# ECG_Monitor.net
KiCad netlist of a schematic drawn in Altium Designer
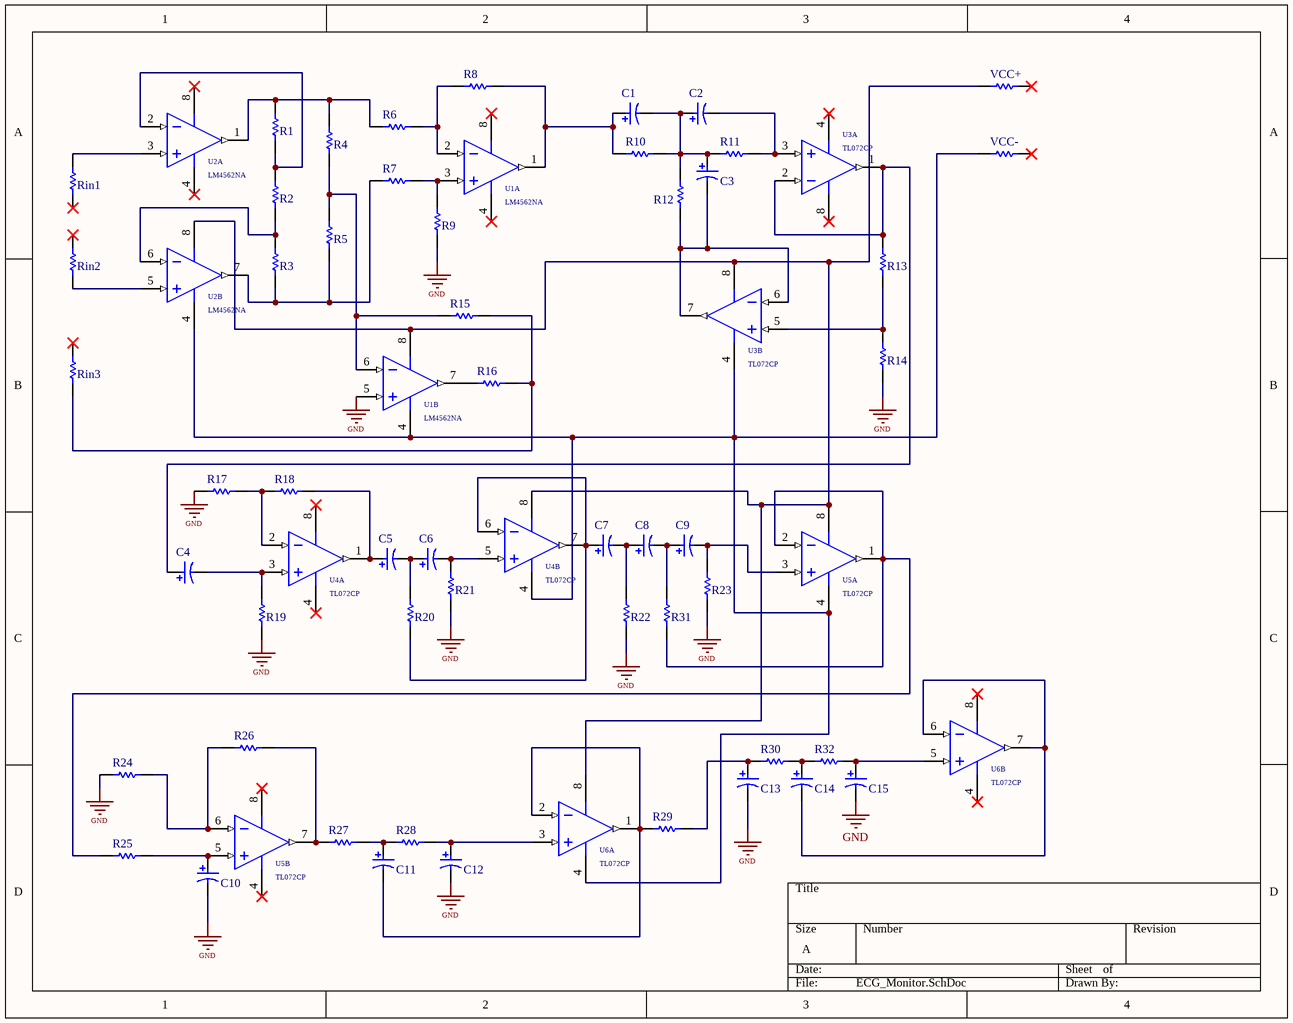
[diagram p0: ECG_Monitor.SchDoc]

(export (version "E")
  (design (tool "Eeschema 10.0.6"))
  (components
    (comp (ref "C1")
      (value "ECA1HM100")
      (footprint "CAPPR55-200-1100X500X1200")
      (description "Aluminum Electrolytic Capacitor, 10 uF, +/- 20%, 50 V, -40 to 85 degC, 2-Pin THD, RoHS, Bulk")
      (fields (field (name "MANUFACTURER") "Panasonic") (field (name "TOLERANCE") "20%"))
      (libsource (lib "Altium Content Vault") (part "CAP-P-2"))
    )
    (comp (ref "C2")
      (value "ECA1HM100")
      (footprint "CAPPR55-200-1100X500X1200")
      (description "Aluminum Electrolytic Capacitor, 10 uF, +/- 20%, 50 V, -40 to 85 degC, 2-Pin THD, RoHS, Bulk")
      (fields (field (name "MANUFACTURER") "Panasonic") (field (name "TOLERANCE") "20%"))
      (libsource (lib "Altium Content Vault") (part "CAP-P-2"))
    )
    (comp (ref "C3")
      (value "ECA1HM100")
      (footprint "CAPPR55-200-1100X500X1200")
      (description "Aluminum Electrolytic Capacitor, 10 uF, +/- 20%, 50 V, -40 to 85 degC, 2-Pin THD, RoHS, Bulk")
      (fields (field (name "MANUFACTURER") "Panasonic") (field (name "TOLERANCE") "20%"))
      (libsource (lib "Altium Content Vault") (part "CAP-P-2"))
    )
    (comp (ref "C4")
      (value "ECA1HM100")
      (footprint "CAPPR55-200-1100X500X1200")
      (description "Aluminum Electrolytic Capacitor, 10 uF, +/- 20%, 50 V, -40 to 85 degC, 2-Pin THD, RoHS, Bulk")
      (fields (field (name "MANUFACTURER") "Panasonic") (field (name "TOLERANCE") "20%"))
      (libsource (lib "Altium Content Vault") (part "CAP-P-2"))
    )
    (comp (ref "C5")
      (value "ECA1HM100")
      (footprint "CAPPR55-200-1100X500X1200")
      (description "Aluminum Electrolytic Capacitor, 10 uF, +/- 20%, 50 V, -40 to 85 degC, 2-Pin THD, RoHS, Bulk")
      (fields (field (name "MANUFACTURER") "Panasonic") (field (name "TOLERANCE") "20%"))
      (libsource (lib "Altium Content Vault") (part "CAP-P-2"))
    )
    (comp (ref "C6")
      (value "ECA1HM100")
      (footprint "CAPPR55-200-1100X500X1200")
      (description "Aluminum Electrolytic Capacitor, 10 uF, +/- 20%, 50 V, -40 to 85 degC, 2-Pin THD, RoHS, Bulk")
      (fields (field (name "MANUFACTURER") "Panasonic") (field (name "TOLERANCE") "20%"))
      (libsource (lib "Altium Content Vault") (part "CAP-P-2"))
    )
    (comp (ref "C7")
      (value "ECA1HM100")
      (footprint "CAPPR55-200-1100X500X1200")
      (description "Aluminum Electrolytic Capacitor, 10 uF, +/- 20%, 50 V, -40 to 85 degC, 2-Pin THD, RoHS, Bulk")
      (fields (field (name "MANUFACTURER") "Panasonic") (field (name "TOLERANCE") "20%"))
      (libsource (lib "Altium Content Vault") (part "CAP-P-2"))
    )
    (comp (ref "C8")
      (value "ECA1HM100")
      (footprint "CAPPR55-200-1100X500X1200")
      (description "Aluminum Electrolytic Capacitor, 10 uF, +/- 20%, 50 V, -40 to 85 degC, 2-Pin THD, RoHS, Bulk")
      (fields (field (name "MANUFACTURER") "Panasonic") (field (name "TOLERANCE") "20%"))
      (libsource (lib "Altium Content Vault") (part "CAP-P-2"))
    )
    (comp (ref "C9")
      (value "ECA1HM100")
      (footprint "CAPPR55-200-1100X500X1200")
      (description "Aluminum Electrolytic Capacitor, 10 uF, +/- 20%, 50 V, -40 to 85 degC, 2-Pin THD, RoHS, Bulk")
      (fields (field (name "MANUFACTURER") "Panasonic") (field (name "TOLERANCE") "20%"))
      (libsource (lib "Altium Content Vault") (part "CAP-P-2"))
    )
    (comp (ref "C10")
      (value "ECA1HM100")
      (footprint "CAPPR55-200-1100X500X1200")
      (description "Aluminum Electrolytic Capacitor, 10 uF, +/- 20%, 50 V, -40 to 85 degC, 2-Pin THD, RoHS, Bulk")
      (fields (field (name "MANUFACTURER") "Panasonic") (field (name "TOLERANCE") "20%"))
      (libsource (lib "Altium Content Vault") (part "CAP-P-2"))
    )
    (comp (ref "C11")
      (value "ECA1HM100")
      (footprint "CAPPR55-200-1100X500X1200")
      (description "Aluminum Electrolytic Capacitor, 10 uF, +/- 20%, 50 V, -40 to 85 degC, 2-Pin THD, RoHS, Bulk")
      (fields (field (name "MANUFACTURER") "Panasonic") (field (name "TOLERANCE") "20%"))
      (libsource (lib "Altium Content Vault") (part "CAP-P-2"))
    )
    (comp (ref "C12")
      (value "ECA1HM100")
      (footprint "CAPPR55-200-1100X500X1200")
      (description "Aluminum Electrolytic Capacitor, 10 uF, +/- 20%, 50 V, -40 to 85 degC, 2-Pin THD, RoHS, Bulk")
      (fields (field (name "MANUFACTURER") "Panasonic") (field (name "TOLERANCE") "20%"))
      (libsource (lib "Altium Content Vault") (part "CAP-P-2"))
    )
    (comp (ref "C13")
      (value "ECA1HM100")
      (footprint "CAPPR55-200-1100X500X1200")
      (description "Aluminum Electrolytic Capacitor, 10 uF, +/- 20%, 50 V, -40 to 85 degC, 2-Pin THD, RoHS, Bulk")
      (fields (field (name "MANUFACTURER") "Panasonic") (field (name "TOLERANCE") "20%"))
      (libsource (lib "Altium Content Vault") (part "CAP-P-2"))
    )
    (comp (ref "C14")
      (value "ECA1HM100")
      (footprint "CAPPR55-200-1100X500X1200")
      (description "Aluminum Electrolytic Capacitor, 10 uF, +/- 20%, 50 V, -40 to 85 degC, 2-Pin THD, RoHS, Bulk")
      (fields (field (name "MANUFACTURER") "Panasonic") (field (name "TOLERANCE") "20%"))
      (libsource (lib "Altium Content Vault") (part "CAP-P-2"))
    )
    (comp (ref "C15")
      (value "ECA1HM100")
      (footprint "CAPPR55-200-1100X500X1200")
      (description "Aluminum Electrolytic Capacitor, 10 uF, +/- 20%, 50 V, -40 to 85 degC, 2-Pin THD, RoHS, Bulk")
      (fields (field (name "MANUFACTURER") "Panasonic") (field (name "TOLERANCE") "20%"))
      (libsource (lib "Altium Content Vault") (part "CAP-P-2"))
    )
    (comp (ref "R1")
      (value "~")
      (footprint "RESA60-630X240")
      (description "Axial Resistor, 221 Ohm, +/- 1%, 250 mW, -55 to 155 degC, 2-Pin THD, RoHS, Bulk")
      (libsource (lib "Altium Content Vault") (part "RES-2"))
    )
    (comp (ref "R2")
      (value "~")
      (footprint "RESA60-630X240")
      (description "Axial Resistor, 221 Ohm, +/- 1%, 250 mW, -55 to 155 degC, 2-Pin THD, RoHS, Bulk")
      (libsource (lib "Altium Content Vault") (part "RES-2"))
    )
    (comp (ref "R3")
      (value "~")
      (footprint "RESA60-630X240")
      (description "Axial Resistor, 221 Ohm, +/- 1%, 250 mW, -55 to 155 degC, 2-Pin THD, RoHS, Bulk")
      (libsource (lib "Altium Content Vault") (part "RES-2"))
    )
    (comp (ref "R4")
      (value "~")
      (footprint "RESA60-630X240")
      (description "Axial Resistor, 221 Ohm, +/- 1%, 250 mW, -55 to 155 degC, 2-Pin THD, RoHS, Bulk")
      (libsource (lib "Altium Content Vault") (part "RES-2"))
    )
    (comp (ref "R5")
      (value "~")
      (footprint "RESA60-630X240")
      (description "Axial Resistor, 221 Ohm, +/- 1%, 250 mW, -55 to 155 degC, 2-Pin THD, RoHS, Bulk")
      (libsource (lib "Altium Content Vault") (part "RES-2"))
    )
    (comp (ref "R6")
      (value "~")
      (footprint "RESA60-630X240")
      (description "Axial Resistor, 221 Ohm, +/- 1%, 250 mW, -55 to 155 degC, 2-Pin THD, RoHS, Bulk")
      (libsource (lib "Altium Content Vault") (part "RES-2"))
    )
    (comp (ref "R7")
      (value "~")
      (footprint "RESA60-630X240")
      (description "Axial Resistor, 221 Ohm, +/- 1%, 250 mW, -55 to 155 degC, 2-Pin THD, RoHS, Bulk")
      (libsource (lib "Altium Content Vault") (part "RES-2"))
    )
    (comp (ref "R8")
      (value "~")
      (footprint "RESA60-630X240")
      (description "Axial Resistor, 221 Ohm, +/- 1%, 250 mW, -55 to 155 degC, 2-Pin THD, RoHS, Bulk")
      (libsource (lib "Altium Content Vault") (part "RES-2"))
    )
    (comp (ref "R9")
      (value "~")
      (footprint "RESA60-630X240")
      (description "Axial Resistor, 221 Ohm, +/- 1%, 250 mW, -55 to 155 degC, 2-Pin THD, RoHS, Bulk")
      (libsource (lib "Altium Content Vault") (part "RES-2"))
    )
    (comp (ref "R10")
      (value "~")
      (footprint "RESA60-630X240")
      (description "Axial Resistor, 221 Ohm, +/- 1%, 250 mW, -55 to 155 degC, 2-Pin THD, RoHS, Bulk")
      (libsource (lib "Altium Content Vault") (part "RES-2"))
    )
    (comp (ref "R11")
      (value "~")
      (footprint "RESA60-630X240")
      (description "Axial Resistor, 221 Ohm, +/- 1%, 250 mW, -55 to 155 degC, 2-Pin THD, RoHS, Bulk")
      (libsource (lib "Altium Content Vault") (part "RES-2"))
    )
    (comp (ref "R12")
      (value "~")
      (footprint "RESA60-630X240")
      (description "Axial Resistor, 221 Ohm, +/- 1%, 250 mW, -55 to 155 degC, 2-Pin THD, RoHS, Bulk")
      (libsource (lib "Altium Content Vault") (part "RES-2"))
    )
    (comp (ref "R13")
      (value "~")
      (footprint "RESA60-630X240")
      (description "Axial Resistor, 221 Ohm, +/- 1%, 250 mW, -55 to 155 degC, 2-Pin THD, RoHS, Bulk")
      (libsource (lib "Altium Content Vault") (part "RES-2"))
    )
    (comp (ref "R14")
      (value "~")
      (footprint "RESA60-630X240")
      (description "Axial Resistor, 221 Ohm, +/- 1%, 250 mW, -55 to 155 degC, 2-Pin THD, RoHS, Bulk")
      (libsource (lib "Altium Content Vault") (part "RES-2"))
    )
    (comp (ref "R15")
      (value "~")
      (footprint "RESA60-630X240")
      (description "Axial Resistor, 221 Ohm, +/- 1%, 250 mW, -55 to 155 degC, 2-Pin THD, RoHS, Bulk")
      (libsource (lib "Altium Content Vault") (part "RES-2"))
    )
    (comp (ref "R16")
      (value "~")
      (footprint "RESA60-630X240")
      (description "Axial Resistor, 221 Ohm, +/- 1%, 250 mW, -55 to 155 degC, 2-Pin THD, RoHS, Bulk")
      (libsource (lib "Altium Content Vault") (part "RES-2"))
    )
    (comp (ref "R17")
      (value "~")
      (footprint "RESA60-630X240")
      (description "Axial Resistor, 221 Ohm, +/- 1%, 250 mW, -55 to 155 degC, 2-Pin THD, RoHS, Bulk")
      (libsource (lib "Altium Content Vault") (part "RES-2"))
    )
    (comp (ref "R18")
      (value "~")
      (footprint "RESA60-630X240")
      (description "Axial Resistor, 221 Ohm, +/- 1%, 250 mW, -55 to 155 degC, 2-Pin THD, RoHS, Bulk")
      (libsource (lib "Altium Content Vault") (part "RES-2"))
    )
    (comp (ref "R19")
      (value "~")
      (footprint "RESA60-630X240")
      (description "Axial Resistor, 221 Ohm, +/- 1%, 250 mW, -55 to 155 degC, 2-Pin THD, RoHS, Bulk")
      (libsource (lib "Altium Content Vault") (part "RES-2"))
    )
    (comp (ref "R20")
      (value "~")
      (footprint "RESA60-630X240")
      (description "Axial Resistor, 221 Ohm, +/- 1%, 250 mW, -55 to 155 degC, 2-Pin THD, RoHS, Bulk")
      (libsource (lib "Altium Content Vault") (part "RES-2"))
    )
    (comp (ref "R21")
      (value "~")
      (footprint "RESA60-630X240")
      (description "Axial Resistor, 221 Ohm, +/- 1%, 250 mW, -55 to 155 degC, 2-Pin THD, RoHS, Bulk")
      (libsource (lib "Altium Content Vault") (part "RES-2"))
    )
    (comp (ref "R22")
      (value "~")
      (footprint "RESA60-630X240")
      (description "Axial Resistor, 221 Ohm, +/- 1%, 250 mW, -55 to 155 degC, 2-Pin THD, RoHS, Bulk")
      (libsource (lib "Altium Content Vault") (part "RES-2"))
    )
    (comp (ref "R23")
      (value "~")
      (footprint "RESA60-630X240")
      (description "Axial Resistor, 221 Ohm, +/- 1%, 250 mW, -55 to 155 degC, 2-Pin THD, RoHS, Bulk")
      (libsource (lib "Altium Content Vault") (part "RES-2"))
    )
    (comp (ref "R24")
      (value "~")
      (footprint "RESA60-630X240")
      (description "Axial Resistor, 221 Ohm, +/- 1%, 250 mW, -55 to 155 degC, 2-Pin THD, RoHS, Bulk")
      (libsource (lib "Altium Content Vault") (part "RES-2"))
    )
    (comp (ref "R25")
      (value "~")
      (footprint "RESA60-630X240")
      (description "Axial Resistor, 221 Ohm, +/- 1%, 250 mW, -55 to 155 degC, 2-Pin THD, RoHS, Bulk")
      (libsource (lib "Altium Content Vault") (part "RES-2"))
    )
    (comp (ref "R26")
      (value "~")
      (footprint "RESA60-630X240")
      (description "Axial Resistor, 221 Ohm, +/- 1%, 250 mW, -55 to 155 degC, 2-Pin THD, RoHS, Bulk")
      (libsource (lib "Altium Content Vault") (part "RES-2"))
    )
    (comp (ref "R27")
      (value "~")
      (footprint "RESA60-630X240")
      (description "Axial Resistor, 221 Ohm, +/- 1%, 250 mW, -55 to 155 degC, 2-Pin THD, RoHS, Bulk")
      (libsource (lib "Altium Content Vault") (part "RES-2"))
    )
    (comp (ref "R28")
      (value "~")
      (footprint "RESA60-630X240")
      (description "Axial Resistor, 221 Ohm, +/- 1%, 250 mW, -55 to 155 degC, 2-Pin THD, RoHS, Bulk")
      (libsource (lib "Altium Content Vault") (part "RES-2"))
    )
    (comp (ref "R29")
      (value "~")
      (footprint "RESA60-630X240")
      (description "Axial Resistor, 221 Ohm, +/- 1%, 250 mW, -55 to 155 degC, 2-Pin THD, RoHS, Bulk")
      (libsource (lib "Altium Content Vault") (part "RES-2"))
    )
    (comp (ref "R30")
      (value "~")
      (footprint "RESA60-630X240")
      (description "Axial Resistor, 221 Ohm, +/- 1%, 250 mW, -55 to 155 degC, 2-Pin THD, RoHS, Bulk")
      (libsource (lib "Altium Content Vault") (part "RES-2"))
    )
    (comp (ref "R31")
      (value "~")
      (footprint "RESA60-630X240")
      (description "Axial Resistor, 221 Ohm, +/- 1%, 250 mW, -55 to 155 degC, 2-Pin THD, RoHS, Bulk")
      (libsource (lib "Altium Content Vault") (part "RES-2"))
    )
    (comp (ref "R32")
      (value "~")
      (footprint "RESA60-630X240")
      (description "Axial Resistor, 221 Ohm, +/- 1%, 250 mW, -55 to 155 degC, 2-Pin THD, RoHS, Bulk")
      (libsource (lib "Altium Content Vault") (part "RES-2"))
    )
    (comp (ref "Rin1")
      (value "~")
      (footprint "RESA60-630X240")
      (description "Axial Resistor, 221 Ohm, +/- 1%, 250 mW, -55 to 155 degC, 2-Pin THD, RoHS, Bulk")
      (libsource (lib "Altium Content Vault") (part "RES-2"))
    )
    (comp (ref "Rin2")
      (value "~")
      (footprint "RESA60-630X240")
      (description "Axial Resistor, 221 Ohm, +/- 1%, 250 mW, -55 to 155 degC, 2-Pin THD, RoHS, Bulk")
      (libsource (lib "Altium Content Vault") (part "RES-2"))
    )
    (comp (ref "Rin3")
      (value "~")
      (footprint "RESA60-630X240")
      (description "Axial Resistor, 221 Ohm, +/- 1%, 250 mW, -55 to 155 degC, 2-Pin THD, RoHS, Bulk")
      (libsource (lib "Altium Content Vault") (part "RES-2"))
    )
    (comp (ref "U1")
      (value "LM4562NA")
      (footprint "N08E")
      (description "Dual High Performance, High Fidelity Audio Operational Amplifier, 8-pin MDIP")
      (fields (field (name "MANUFACTURER") "National Semiconductor"))
      (libsource (lib "Altium Content Vault") (part "AMP-AUDA-LM4562-8"))
    )
    (comp (ref "U2")
      (value "LM4562NA")
      (footprint "N08E")
      (description "Dual High Performance, High Fidelity Audio Operational Amplifier, 8-pin MDIP")
      (fields (field (name "MANUFACTURER") "National Semiconductor"))
      (libsource (lib "Altium Content Vault") (part "AMP-AUDA-LM4562-8"))
    )
    (comp (ref "U3")
      (value "TL072CP")
      (footprint "P0008A")
      (fields (field (name "MANUFACTURER") "Texas Instruments"))
      (libsource (lib "Altium Content Vault") (part "TI-AMP-D6-2-8_D"))
    )
    (comp (ref "U4")
      (value "TL072CP")
      (footprint "P0008A")
      (fields (field (name "MANUFACTURER") "Texas Instruments"))
      (libsource (lib "Altium Content Vault") (part "TI-AMP-D6-2-8_D"))
    )
    (comp (ref "U5")
      (value "TL072CP")
      (footprint "P0008A")
      (fields (field (name "MANUFACTURER") "Texas Instruments"))
      (libsource (lib "Altium Content Vault") (part "TI-AMP-D6-2-8_D"))
    )
    (comp (ref "U6")
      (value "TL072CP")
      (footprint "P0008A")
      (fields (field (name "MANUFACTURER") "Texas Instruments"))
      (libsource (lib "Altium Content Vault") (part "TI-AMP-D6-2-8_D"))
    )
    (comp (ref "VCC+")
      (value "~")
      (footprint "RESA60-630X240")
      (description "Axial Resistor, 221 Ohm, +/- 1%, 250 mW, -55 to 155 degC, 2-Pin THD, RoHS, Bulk")
      (libsource (lib "Altium Content Vault") (part "RES-2"))
    )
    (comp (ref "VCC-")
      (value "~")
      (footprint "RESA60-630X240")
      (description "Axial Resistor, 221 Ohm, +/- 1%, 250 mW, -55 to 155 degC, 2-Pin THD, RoHS, Bulk")
      (libsource (lib "Altium Content Vault") (part "RES-2"))
    )
  )
  (nets
    (net (code "1") (name "GND") (class "Default")
      (node (ref "C10") (pin "2") (pinfunction "2_2") (pintype "passive"))
      (node (ref "C12") (pin "2") (pinfunction "2_2") (pintype "passive"))
      (node (ref "C13") (pin "2") (pinfunction "2_2") (pintype "passive"))
      (node (ref "C15") (pin "2") (pinfunction "2_2") (pintype "passive"))
      (node (ref "R14") (pin "1") (pinfunction "1_1") (pintype "passive"))
      (node (ref "R17") (pin "1") (pinfunction "1_1") (pintype "passive"))
      (node (ref "R19") (pin "1") (pinfunction "1_1") (pintype "passive"))
      (node (ref "R21") (pin "1") (pinfunction "1_1") (pintype "passive"))
      (node (ref "R22") (pin "1") (pinfunction "1_1") (pintype "passive"))
      (node (ref "R23") (pin "1") (pinfunction "1_1") (pintype "passive"))
      (node (ref "R24") (pin "1") (pinfunction "1_1") (pintype "passive"))
      (node (ref "R9") (pin "1") (pinfunction "1_1") (pintype "passive"))
      (node (ref "U1") (pin "5") (pinfunction "IN_B_5") (pintype "input"))
    )
    (net (code "2") (name "Net-(C1-Pad2)") (class "Default")
      (node (ref "C1") (pin "2") (pinfunction "2_2") (pintype "passive"))
      (node (ref "C2") (pin "1") (pinfunction "1_1") (pintype "passive"))
      (node (ref "C3") (pin "1") (pinfunction "1_1") (pintype "passive"))
      (node (ref "R10") (pin "2") (pinfunction "2_2") (pintype "passive"))
      (node (ref "R11") (pin "1") (pinfunction "1_1") (pintype "passive"))
      (node (ref "R12") (pin "2") (pinfunction "2_2") (pintype "passive"))
    )
    (net (code "3") (name "Net-(C5-Pad2)") (class "Default")
      (node (ref "C5") (pin "2") (pinfunction "2_2") (pintype "passive"))
      (node (ref "C6") (pin "1") (pinfunction "1_1") (pintype "passive"))
      (node (ref "R20") (pin "2") (pinfunction "2_2") (pintype "passive"))
    )
    (net (code "4") (name "Net-(C7-Pad2)") (class "Default")
      (node (ref "C7") (pin "2") (pinfunction "2_2") (pintype "passive"))
      (node (ref "C8") (pin "1") (pinfunction "1_1") (pintype "passive"))
      (node (ref "R22") (pin "2") (pinfunction "2_2") (pintype "passive"))
    )
    (net (code "5") (name "Net-(C8-Pad2)") (class "Default")
      (node (ref "C8") (pin "2") (pinfunction "2_2") (pintype "passive"))
      (node (ref "C9") (pin "1") (pinfunction "1_1") (pintype "passive"))
      (node (ref "R31") (pin "2") (pinfunction "2_2") (pintype "passive"))
    )
    (net (code "6") (name "Net-(C11-Pad1)") (class "Default")
      (node (ref "C11") (pin "1") (pinfunction "1_1") (pintype "passive"))
      (node (ref "R27") (pin "2") (pinfunction "2_2") (pintype "passive"))
      (node (ref "R28") (pin "1") (pinfunction "1_1") (pintype "passive"))
    )
    (net (code "7") (name "Net-(C13-Pad1)") (class "Default")
      (node (ref "C13") (pin "1") (pinfunction "1_1") (pintype "passive"))
      (node (ref "R29") (pin "2") (pinfunction "2_2") (pintype "passive"))
      (node (ref "R30") (pin "1") (pinfunction "1_1") (pintype "passive"))
    )
    (net (code "8") (name "Net-(C14-Pad1)") (class "Default")
      (node (ref "C14") (pin "1") (pinfunction "1_1") (pintype "passive"))
      (node (ref "R30") (pin "2") (pinfunction "2_2") (pintype "passive"))
      (node (ref "R32") (pin "1") (pinfunction "1_1") (pintype "passive"))
    )
    (net (code "9") (name "Net-(R1-Pad1)") (class "Default")
      (node (ref "R1") (pin "1") (pinfunction "1_1") (pintype "passive"))
      (node (ref "R2") (pin "2") (pinfunction "2_2") (pintype "passive"))
      (node (ref "U2") (pin "2") (pinfunction "IN_A_2") (pintype "input"))
    )
    (net (code "10") (name "Net-(R2-Pad1)") (class "Default")
      (node (ref "R2") (pin "1") (pinfunction "1_1") (pintype "passive"))
      (node (ref "R3") (pin "2") (pinfunction "2_2") (pintype "passive"))
      (node (ref "U2") (pin "6") (pinfunction "IN_B_6") (pintype "input"))
    )
    (net (code "11") (name "Net-(R6-Pad2)") (class "Default")
      (node (ref "R6") (pin "2") (pinfunction "2_2") (pintype "passive"))
      (node (ref "R8") (pin "1") (pinfunction "1_1") (pintype "passive"))
      (node (ref "U1") (pin "2") (pinfunction "IN_A_2") (pintype "input"))
    )
    (net (code "12") (name "Net-(R7-Pad2)") (class "Default")
      (node (ref "R7") (pin "2") (pinfunction "2_2") (pintype "passive"))
      (node (ref "R9") (pin "2") (pinfunction "2_2") (pintype "passive"))
      (node (ref "U1") (pin "3") (pinfunction "IN_A_3") (pintype "input"))
    )
    (net (code "13") (name "Net-(R15-Pad1)") (class "Default")
      (node (ref "R15") (pin "1") (pinfunction "1_1") (pintype "passive"))
      (node (ref "R4") (pin "1") (pinfunction "1_1") (pintype "passive"))
      (node (ref "R5") (pin "2") (pinfunction "2_2") (pintype "passive"))
      (node (ref "U1") (pin "6") (pinfunction "IN_B_6") (pintype "input"))
    )
    (net (code "14") (name "Net-(R15-Pad2)") (class "Default")
      (node (ref "R15") (pin "2") (pinfunction "2_2") (pintype "passive"))
      (node (ref "R16") (pin "2") (pinfunction "2_2") (pintype "passive"))
      (node (ref "Rin3") (pin "1") (pinfunction "1_1") (pintype "passive"))
    )
    (net (code "15") (name "Net-(Rin1-Pad2)") (class "Default")
      (node (ref "Rin1") (pin "2") (pinfunction "2_2") (pintype "passive"))
      (node (ref "U2") (pin "3") (pinfunction "IN_A_3") (pintype "input"))
    )
    (net (code "16") (name "Net-(Rin2-Pad1)") (class "Default")
      (node (ref "Rin2") (pin "1") (pinfunction "1_1") (pintype "passive"))
      (node (ref "U2") (pin "5") (pinfunction "IN_B_5") (pintype "input"))
    )
    (net (code "17") (name "Net-(U1A-OUT_A)") (class "Default")
      (node (ref "C1") (pin "1") (pinfunction "1_1") (pintype "passive"))
      (node (ref "R10") (pin "1") (pinfunction "1_1") (pintype "passive"))
      (node (ref "R8") (pin "2") (pinfunction "2_2") (pintype "passive"))
      (node (ref "U1") (pin "1") (pinfunction "OUT_A_1") (pintype "output"))
    )
    (net (code "18") (name "Net-(U1B-OUT_B)") (class "Default")
      (node (ref "R16") (pin "1") (pinfunction "1_1") (pintype "passive"))
      (node (ref "U1") (pin "7") (pinfunction "OUT_B_7") (pintype "output"))
    )
    (net (code "19") (name "Net-(U1B-V+)") (class "Default")
      (node (ref "U1") (pin "8") (pinfunction "V+_8") (pintype "power_in"))
      (node (ref "U2") (pin "8") (pinfunction "V+_8") (pintype "power_in"))
      (node (ref "U3") (pin "8") (pinfunction "VCC+_8") (pintype "power_in"))
      (node (ref "U4") (pin "8") (pinfunction "VCC+_8") (pintype "power_in"))
      (node (ref "U5") (pin "8") (pinfunction "VCC+_8") (pintype "power_in"))
      (node (ref "U6") (pin "8") (pinfunction "VCC+_8") (pintype "power_in"))
      (node (ref "VCC+") (pin "1") (pinfunction "1_1") (pintype "passive"))
    )
    (net (code "20") (name "Net-(U1B-V-)") (class "Default")
      (node (ref "U1") (pin "4") (pinfunction "V-_4") (pintype "power_in"))
      (node (ref "U2") (pin "4") (pinfunction "V-_4") (pintype "power_in"))
      (node (ref "U3") (pin "4") (pinfunction "VCC-_4") (pintype "power_in"))
      (node (ref "U4") (pin "4") (pinfunction "VCC-_4") (pintype "power_in"))
      (node (ref "U5") (pin "4") (pinfunction "VCC-_4") (pintype "power_in"))
      (node (ref "U6") (pin "4") (pinfunction "VCC-_4") (pintype "power_in"))
      (node (ref "VCC-") (pin "1") (pinfunction "1_1") (pintype "passive"))
    )
    (net (code "21") (name "Net-(U2A-OUT_A)") (class "Default")
      (node (ref "R1") (pin "2") (pinfunction "2_2") (pintype "passive"))
      (node (ref "R4") (pin "2") (pinfunction "2_2") (pintype "passive"))
      (node (ref "R6") (pin "1") (pinfunction "1_1") (pintype "passive"))
      (node (ref "U2") (pin "1") (pinfunction "OUT_A_1") (pintype "output"))
    )
    (net (code "22") (name "Net-(U2B-OUT_B)") (class "Default")
      (node (ref "R3") (pin "1") (pinfunction "1_1") (pintype "passive"))
      (node (ref "R5") (pin "1") (pinfunction "1_1") (pintype "passive"))
      (node (ref "R7") (pin "1") (pinfunction "1_1") (pintype "passive"))
      (node (ref "U2") (pin "7") (pinfunction "OUT_B_7") (pintype "output"))
    )
    (net (code "23") (name "Net-(U3A-IN1+)") (class "Default")
      (node (ref "C2") (pin "2") (pinfunction "2_2") (pintype "passive"))
      (node (ref "R11") (pin "2") (pinfunction "2_2") (pintype "passive"))
      (node (ref "U3") (pin "3") (pinfunction "IN1+_3") (pintype "input"))
    )
    (net (code "24") (name "Net-(U3A-IN1-)") (class "Default")
      (node (ref "C4") (pin "1") (pinfunction "1_1") (pintype "passive"))
      (node (ref "R13") (pin "2") (pinfunction "2_2") (pintype "passive"))
      (node (ref "U3") (pin "1") (pinfunction "OUT1_1") (pintype "output"))
      (node (ref "U3") (pin "2") (pinfunction "IN1-_2") (pintype "input"))
    )
    (net (code "25") (name "Net-(U3B-IN2+)") (class "Default")
      (node (ref "R13") (pin "1") (pinfunction "1_1") (pintype "passive"))
      (node (ref "R14") (pin "2") (pinfunction "2_2") (pintype "passive"))
      (node (ref "U3") (pin "5") (pinfunction "IN2+_5") (pintype "input"))
    )
    (net (code "26") (name "Net-(U3B-IN2-)") (class "Default")
      (node (ref "C3") (pin "2") (pinfunction "2_2") (pintype "passive"))
      (node (ref "R12") (pin "1") (pinfunction "1_1") (pintype "passive"))
      (node (ref "U3") (pin "6") (pinfunction "IN2-_6") (pintype "input"))
      (node (ref "U3") (pin "7") (pinfunction "OUT2_7") (pintype "output"))
    )
    (net (code "27") (name "Net-(U4A-IN1+)") (class "Default")
      (node (ref "C4") (pin "2") (pinfunction "2_2") (pintype "passive"))
      (node (ref "R19") (pin "2") (pinfunction "2_2") (pintype "passive"))
      (node (ref "U4") (pin "3") (pinfunction "IN1+_3") (pintype "input"))
    )
    (net (code "28") (name "Net-(U4A-IN1-)") (class "Default")
      (node (ref "R17") (pin "2") (pinfunction "2_2") (pintype "passive"))
      (node (ref "R18") (pin "1") (pinfunction "1_1") (pintype "passive"))
      (node (ref "U4") (pin "2") (pinfunction "IN1-_2") (pintype "input"))
    )
    (net (code "29") (name "Net-(U4A-OUT1)") (class "Default")
      (node (ref "C5") (pin "1") (pinfunction "1_1") (pintype "passive"))
      (node (ref "R18") (pin "2") (pinfunction "2_2") (pintype "passive"))
      (node (ref "U4") (pin "1") (pinfunction "OUT1_1") (pintype "output"))
    )
    (net (code "30") (name "Net-(U4B-IN2+)") (class "Default")
      (node (ref "C6") (pin "2") (pinfunction "2_2") (pintype "passive"))
      (node (ref "R21") (pin "2") (pinfunction "2_2") (pintype "passive"))
      (node (ref "U4") (pin "5") (pinfunction "IN2+_5") (pintype "input"))
    )
    (net (code "31") (name "Net-(U4B-IN2-)") (class "Default")
      (node (ref "C7") (pin "1") (pinfunction "1_1") (pintype "passive"))
      (node (ref "R20") (pin "1") (pinfunction "1_1") (pintype "passive"))
      (node (ref "U4") (pin "6") (pinfunction "IN2-_6") (pintype "input"))
      (node (ref "U4") (pin "7") (pinfunction "OUT2_7") (pintype "output"))
    )
    (net (code "32") (name "Net-(U5A-IN1+)") (class "Default")
      (node (ref "C9") (pin "2") (pinfunction "2_2") (pintype "passive"))
      (node (ref "R23") (pin "2") (pinfunction "2_2") (pintype "passive"))
      (node (ref "U5") (pin "3") (pinfunction "IN1+_3") (pintype "input"))
    )
    (net (code "33") (name "Net-(U5A-IN1-)") (class "Default")
      (node (ref "R25") (pin "1") (pinfunction "1_1") (pintype "passive"))
      (node (ref "R31") (pin "1") (pinfunction "1_1") (pintype "passive"))
      (node (ref "U5") (pin "1") (pinfunction "OUT1_1") (pintype "output"))
      (node (ref "U5") (pin "2") (pinfunction "IN1-_2") (pintype "input"))
    )
    (net (code "34") (name "Net-(U5B-IN2+)") (class "Default")
      (node (ref "C10") (pin "1") (pinfunction "1_1") (pintype "passive"))
      (node (ref "R25") (pin "2") (pinfunction "2_2") (pintype "passive"))
      (node (ref "U5") (pin "5") (pinfunction "IN2+_5") (pintype "input"))
    )
    (net (code "35") (name "Net-(U5B-IN2-)") (class "Default")
      (node (ref "R24") (pin "2") (pinfunction "2_2") (pintype "passive"))
      (node (ref "R26") (pin "1") (pinfunction "1_1") (pintype "passive"))
      (node (ref "U5") (pin "6") (pinfunction "IN2-_6") (pintype "input"))
    )
    (net (code "36") (name "Net-(U5B-OUT2)") (class "Default")
      (node (ref "R26") (pin "2") (pinfunction "2_2") (pintype "passive"))
      (node (ref "R27") (pin "1") (pinfunction "1_1") (pintype "passive"))
      (node (ref "U5") (pin "7") (pinfunction "OUT2_7") (pintype "output"))
    )
    (net (code "37") (name "Net-(U6A-IN1+)") (class "Default")
      (node (ref "C12") (pin "1") (pinfunction "1_1") (pintype "passive"))
      (node (ref "R28") (pin "2") (pinfunction "2_2") (pintype "passive"))
      (node (ref "U6") (pin "3") (pinfunction "IN1+_3") (pintype "input"))
    )
    (net (code "38") (name "Net-(U6A-IN1-)") (class "Default")
      (node (ref "C11") (pin "2") (pinfunction "2_2") (pintype "passive"))
      (node (ref "R29") (pin "1") (pinfunction "1_1") (pintype "passive"))
      (node (ref "U6") (pin "1") (pinfunction "OUT1_1") (pintype "output"))
      (node (ref "U6") (pin "2") (pinfunction "IN1-_2") (pintype "input"))
    )
    (net (code "39") (name "Net-(U6B-IN2+)") (class "Default")
      (node (ref "C15") (pin "1") (pinfunction "1_1") (pintype "passive"))
      (node (ref "R32") (pin "2") (pinfunction "2_2") (pintype "passive"))
      (node (ref "U6") (pin "5") (pinfunction "IN2+_5") (pintype "input"))
    )
    (net (code "40") (name "Net-(U6B-IN2-)") (class "Default")
      (node (ref "C14") (pin "2") (pinfunction "2_2") (pintype "passive"))
      (node (ref "U6") (pin "6") (pinfunction "IN2-_6") (pintype "input"))
      (node (ref "U6") (pin "7") (pinfunction "OUT2_7") (pintype "output"))
    )
    (net (code "41") (name "unconnected-(Rin1-Pad1)") (class "Default")
      (node (ref "Rin1") (pin "1") (pinfunction "1_1") (pintype "passive+no_connect"))
    )
    (net (code "42") (name "unconnected-(Rin2-Pad2)") (class "Default")
      (node (ref "Rin2") (pin "2") (pinfunction "2_2") (pintype "passive+no_connect"))
    )
    (net (code "43") (name "unconnected-(Rin3-Pad2)") (class "Default")
      (node (ref "Rin3") (pin "2") (pinfunction "2_2") (pintype "passive+no_connect"))
    )
    (net (code "44") (name "unconnected-(U1A-V+-Pad8)") (class "Default")
      (node (ref "U1") (pin "8") (pinfunction "V+_8") (pintype "power_in+no_connect"))
    )
    (net (code "45") (name "unconnected-(U1A-V--Pad4)") (class "Default")
      (node (ref "U1") (pin "4") (pinfunction "V-_4") (pintype "power_in+no_connect"))
    )
    (net (code "46") (name "unconnected-(U2A-V+-Pad8)") (class "Default")
      (node (ref "U2") (pin "8") (pinfunction "V+_8") (pintype "power_in+no_connect"))
    )
    (net (code "47") (name "unconnected-(U2A-V--Pad4)") (class "Default")
      (node (ref "U2") (pin "4") (pinfunction "V-_4") (pintype "power_in+no_connect"))
    )
    (net (code "48") (name "unconnected-(U3A-VCC+-Pad8)") (class "Default")
      (node (ref "U3") (pin "8") (pinfunction "VCC+_8") (pintype "power_in+no_connect"))
    )
    (net (code "49") (name "unconnected-(U3A-VCC--Pad4)") (class "Default")
      (node (ref "U3") (pin "4") (pinfunction "VCC-_4") (pintype "power_in+no_connect"))
    )
    (net (code "50") (name "unconnected-(U4A-VCC+-Pad8)") (class "Default")
      (node (ref "U4") (pin "8") (pinfunction "VCC+_8") (pintype "power_in+no_connect"))
    )
    (net (code "51") (name "unconnected-(U4A-VCC--Pad4)") (class "Default")
      (node (ref "U4") (pin "4") (pinfunction "VCC-_4") (pintype "power_in+no_connect"))
    )
    (net (code "52") (name "unconnected-(U5B-VCC+-Pad8)") (class "Default")
      (node (ref "U5") (pin "8") (pinfunction "VCC+_8") (pintype "power_in+no_connect"))
    )
    (net (code "53") (name "unconnected-(U5B-VCC--Pad4)") (class "Default")
      (node (ref "U5") (pin "4") (pinfunction "VCC-_4") (pintype "power_in+no_connect"))
    )
    (net (code "54") (name "unconnected-(U6B-VCC+-Pad8)") (class "Default")
      (node (ref "U6") (pin "8") (pinfunction "VCC+_8") (pintype "power_in+no_connect"))
    )
    (net (code "55") (name "unconnected-(U6B-VCC--Pad4)") (class "Default")
      (node (ref "U6") (pin "4") (pinfunction "VCC-_4") (pintype "power_in+no_connect"))
    )
    (net (code "56") (name "unconnected-(VCC+-Pad2)") (class "Default")
      (node (ref "VCC+") (pin "2") (pinfunction "2_2") (pintype "passive+no_connect"))
    )
    (net (code "57") (name "unconnected-(VCC--Pad2)") (class "Default")
      (node (ref "VCC-") (pin "2") (pinfunction "2_2") (pintype "passive+no_connect"))
    )
  )
)
